# POWER_BANK_PART.net
KiCad netlist of a schematic drawn in Altium Designer
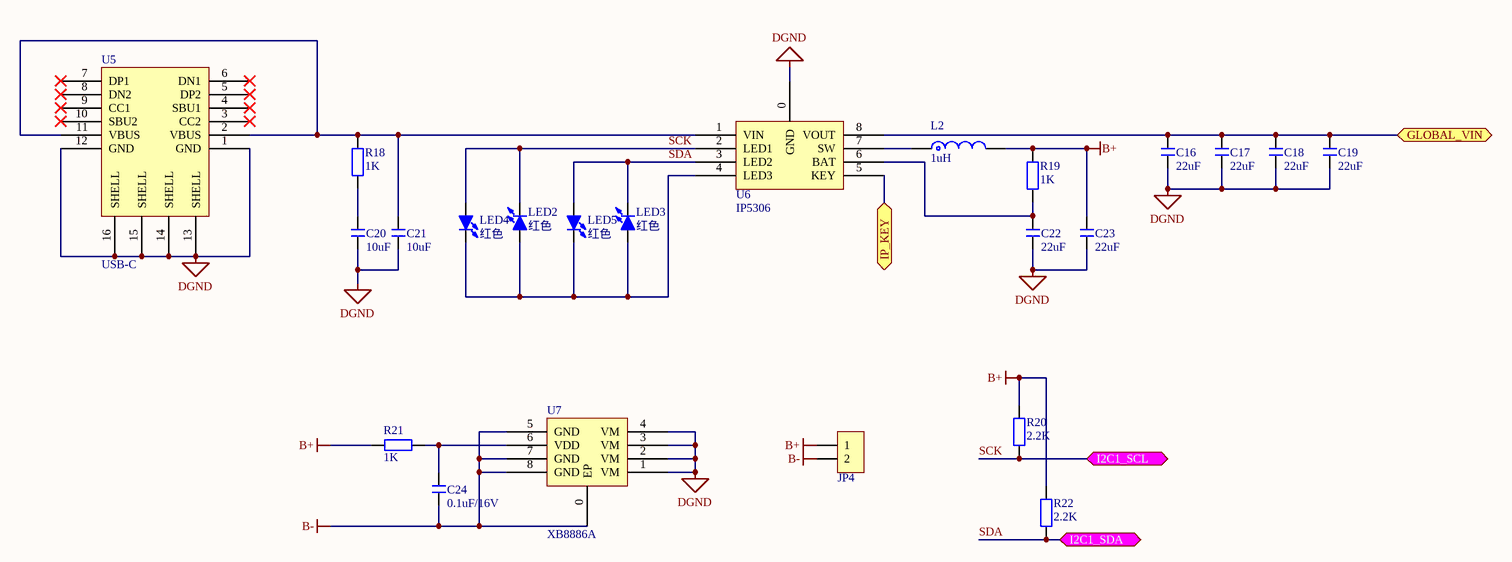
[diagram p0: POWER_BANK_PART.SchDoc]

(export (version "E")
  (design (tool "Eeschema 10.0.6"))
  (components
    (comp (ref "C16")
      (value "22uF")
      (footprint "C 0603_L")
      (description "无极性贴片电容")
      (fields (field (name "版权归属") "源创客"))
      (libsource (lib "3.1   - 电阻-电容-电感") (part "C"))
    )
    (comp (ref "C17")
      (value "22uF")
      (footprint "C 0603_L")
      (description "无极性贴片电容")
      (fields (field (name "版权归属") "源创客"))
      (libsource (lib "3.1   - 电阻-电容-电感") (part "C"))
    )
    (comp (ref "C18")
      (value "22uF")
      (footprint "C 0603_L")
      (description "无极性贴片电容")
      (fields (field (name "版权归属") "源创客"))
      (libsource (lib "3.1   - 电阻-电容-电感") (part "C"))
    )
    (comp (ref "C19")
      (value "22uF")
      (footprint "C 0603_L")
      (description "无极性贴片电容")
      (fields (field (name "版权归属") "源创客"))
      (libsource (lib "3.1   - 电阻-电容-电感") (part "C"))
    )
    (comp (ref "C20")
      (value "10uF")
      (footprint "C 0603_L")
      (description "无极性贴片电容")
      (fields (field (name "版权归属") "源创客"))
      (libsource (lib "3.1   - 电阻-电容-电感") (part "C"))
    )
    (comp (ref "C21")
      (value "10uF")
      (footprint "C 0603_L")
      (description "无极性贴片电容")
      (fields (field (name "版权归属") "源创客"))
      (libsource (lib "3.1   - 电阻-电容-电感") (part "C"))
    )
    (comp (ref "C22")
      (value "22uF")
      (footprint "C 0603_L")
      (description "无极性贴片电容")
      (fields (field (name "版权归属") "源创客"))
      (libsource (lib "3.1   - 电阻-电容-电感") (part "C"))
    )
    (comp (ref "C23")
      (value "22uF")
      (footprint "C 0603_L")
      (description "无极性贴片电容")
      (fields (field (name "版权归属") "源创客"))
      (libsource (lib "3.1   - 电阻-电容-电感") (part "C"))
    )
    (comp (ref "C24")
      (value "0.1uF/16V")
      (footprint "C 0603_L")
      (description "无极性贴片电容")
      (fields (field (name "版权归属") "源创客"))
      (libsource (lib "3.1   - 电阻-电容-电感") (part "C"))
    )
    (comp (ref "JP4")
      (value "HDR-1X2")
      (footprint "KF301-5.0-2P")
      (description "2P接插件")
      (fields (field (name "版权归属") "源创客"))
      (libsource (lib "4.9   - 接插件-脚距5.0") (part "Header 2"))
    )
    (comp (ref "L2")
      (value "1uH")
      (footprint "CD43")
      (description "贴片功率电感")
      (fields (field (name "版权归属") "源创客"))
      (libsource (lib "3.1   - 电阻-电容-电感") (part "L-CD"))
    )
    (comp (ref "LED2")
      (value "红色")
      (footprint "LED 0603W")
      (description "贴片LED")
      (fields (field (name "版权归属") "源创客"))
      (libsource (lib "9.1   - LED") (part "LED-SMD"))
    )
    (comp (ref "LED3")
      (value "红色")
      (footprint "LED 0603W")
      (description "贴片LED")
      (fields (field (name "版权归属") "源创客"))
      (libsource (lib "9.1   - LED") (part "LED-SMD"))
    )
    (comp (ref "LED4")
      (value "红色")
      (footprint "LED 0603W")
      (description "贴片LED")
      (fields (field (name "版权归属") "源创客"))
      (libsource (lib "9.1   - LED") (part "LED-SMD"))
    )
    (comp (ref "LED5")
      (value "红色")
      (footprint "LED 0603W")
      (description "贴片LED")
      (fields (field (name "版权归属") "源创客"))
      (libsource (lib "9.1   - LED") (part "LED-SMD"))
    )
    (comp (ref "R18")
      (value "1K")
      (footprint "R 0603_L")
      (description "贴片电阻")
      (fields (field (name "版权归属") "源创客"))
      (libsource (lib "3.1   - 电阻-电容-电感") (part "R"))
    )
    (comp (ref "R19")
      (value "1K")
      (footprint "R 0603_L")
      (description "贴片电阻")
      (fields (field (name "版权归属") "源创客"))
      (libsource (lib "3.1   - 电阻-电容-电感") (part "R"))
    )
    (comp (ref "R20")
      (value "2.2K")
      (footprint "R 0603_L")
      (description "贴片电阻")
      (fields (field (name "版权归属") "源创客"))
      (libsource (lib "3.1   - 电阻-电容-电感") (part "R"))
    )
    (comp (ref "R21")
      (value "1K")
      (footprint "R 0603_L")
      (description "贴片电阻")
      (fields (field (name "版权归属") "源创客"))
      (libsource (lib "3.1   - 电阻-电容-电感") (part "R"))
    )
    (comp (ref "R22")
      (value "2.2K")
      (footprint "R 0603_L")
      (description "贴片电阻")
      (fields (field (name "版权归属") "源创客"))
      (libsource (lib "3.1   - 电阻-电容-电感") (part "R"))
    )
    (comp (ref "U5")
      (value "USB-C")
      (footprint "USB-C-16")
      (description "USB-C型母接口")
      (fields (field (name "版权归属") "源创客"))
      (libsource (lib "示波器") (part "USB-C-16P"))
    )
    (comp (ref "U6")
      (value "IP5306")
      (footprint "SOP-8-G")
      (description "电源芯片")
      (libsource (lib "示波器") (part "IP5306"))
    )
    (comp (ref "U7")
      (value "XB8886A")
      (footprint "SOP-8-G")
      (description "锂电池保护芯片")
      (libsource (lib "示波器") (part "XB8886A"))
    )
  )
  (nets
    (net (code "1") (name "/GLOBAL_VIN") (class "Default")
      (node (ref "C16") (pin "1") (pinfunction "1_1") (pintype "passive"))
      (node (ref "C17") (pin "1") (pinfunction "1_1") (pintype "passive"))
      (node (ref "C18") (pin "1") (pinfunction "1_1") (pintype "passive"))
      (node (ref "C19") (pin "1") (pinfunction "1_1") (pintype "passive"))
      (node (ref "U6") (pin "8") (pinfunction "VOUT_8") (pintype "passive"))
    )
    (net (code "2") (name "/IP_KEY") (class "Default")
      (node (ref "U6") (pin "5") (pinfunction "KEY_5") (pintype "passive"))
    )
    (net (code "3") (name "/SCK") (class "Default")
      (node (ref "LED2") (pin "2") (pinfunction "K_2") (pintype "passive"))
      (node (ref "LED4") (pin "1") (pinfunction "A_1") (pintype "passive"))
      (node (ref "R20") (pin "1") (pinfunction "1_1") (pintype "passive"))
      (node (ref "U6") (pin "2") (pinfunction "LED1_2") (pintype "passive"))
    )
    (net (code "4") (name "/SDA") (class "Default")
      (node (ref "LED3") (pin "2") (pinfunction "K_2") (pintype "passive"))
      (node (ref "LED5") (pin "1") (pinfunction "A_1") (pintype "passive"))
      (node (ref "R22") (pin "1") (pinfunction "1_1") (pintype "passive"))
      (node (ref "U6") (pin "3") (pinfunction "LED2_3") (pintype "passive"))
    )
    (net (code "5") (name "B+") (class "Default")
      (node (ref "C23") (pin "1") (pinfunction "1_1") (pintype "passive"))
      (node (ref "JP4") (pin "1") (pinfunction "1_1") (pintype "passive"))
      (node (ref "L2") (pin "2") (pinfunction "2_2") (pintype "passive"))
      (node (ref "R19") (pin "2") (pinfunction "2_2") (pintype "passive"))
      (node (ref "R20") (pin "2") (pinfunction "2_2") (pintype "passive"))
      (node (ref "R21") (pin "1") (pinfunction "1_1") (pintype "passive"))
      (node (ref "R22") (pin "2") (pinfunction "2_2") (pintype "passive"))
    )
    (net (code "6") (name "B-") (class "Default")
      (node (ref "C24") (pin "2") (pinfunction "2_2") (pintype "passive"))
      (node (ref "JP4") (pin "2") (pinfunction "2_2") (pintype "passive"))
      (node (ref "U7") (pin "0") (pinfunction "EP_0") (pintype "passive"))
      (node (ref "U7") (pin "5") (pinfunction "GND_5") (pintype "passive"))
      (node (ref "U7") (pin "7") (pinfunction "GND_7") (pintype "passive"))
      (node (ref "U7") (pin "8") (pinfunction "GND_8") (pintype "passive"))
    )
    (net (code "7") (name "DGND") (class "Default")
      (node (ref "C16") (pin "2") (pinfunction "2_2") (pintype "passive"))
      (node (ref "C17") (pin "2") (pinfunction "2_2") (pintype "passive"))
      (node (ref "C18") (pin "2") (pinfunction "2_2") (pintype "passive"))
      (node (ref "C19") (pin "2") (pinfunction "2_2") (pintype "passive"))
      (node (ref "C20") (pin "2") (pinfunction "2_2") (pintype "passive"))
      (node (ref "C21") (pin "2") (pinfunction "2_2") (pintype "passive"))
      (node (ref "C22") (pin "2") (pinfunction "2_2") (pintype "passive"))
      (node (ref "C23") (pin "2") (pinfunction "2_2") (pintype "passive"))
      (node (ref "U5") (pin "1") (pinfunction "GND_1") (pintype "passive"))
      (node (ref "U5") (pin "12") (pinfunction "GND_12") (pintype "passive"))
      (node (ref "U5") (pin "13") (pinfunction "SHELL_13") (pintype "passive"))
      (node (ref "U5") (pin "14") (pinfunction "SHELL_14") (pintype "passive"))
      (node (ref "U5") (pin "15") (pinfunction "SHELL_15") (pintype "passive"))
      (node (ref "U5") (pin "16") (pinfunction "SHELL_16") (pintype "passive"))
      (node (ref "U6") (pin "0") (pinfunction "GND_0") (pintype "passive"))
      (node (ref "U7") (pin "1") (pinfunction "VM_1") (pintype "passive"))
      (node (ref "U7") (pin "2") (pinfunction "VM_2") (pintype "passive"))
      (node (ref "U7") (pin "3") (pinfunction "VM_3") (pintype "passive"))
      (node (ref "U7") (pin "4") (pinfunction "VM_4") (pintype "passive"))
    )
    (net (code "8") (name "Net-(C20-Pad1)") (class "Default")
      (node (ref "C20") (pin "1") (pinfunction "1_1") (pintype "passive"))
      (node (ref "R18") (pin "1") (pinfunction "1_1") (pintype "passive"))
    )
    (net (code "9") (name "Net-(LED2-A)") (class "Default")
      (node (ref "LED2") (pin "1") (pinfunction "A_1") (pintype "passive"))
      (node (ref "LED3") (pin "1") (pinfunction "A_1") (pintype "passive"))
      (node (ref "LED4") (pin "2") (pinfunction "K_2") (pintype "passive"))
      (node (ref "LED5") (pin "2") (pinfunction "K_2") (pintype "passive"))
      (node (ref "U6") (pin "4") (pinfunction "LED3_4") (pintype "passive"))
    )
    (net (code "10") (name "Net-(U6-BAT)") (class "Default")
      (node (ref "C22") (pin "1") (pinfunction "1_1") (pintype "passive"))
      (node (ref "R19") (pin "1") (pinfunction "1_1") (pintype "passive"))
      (node (ref "U6") (pin "6") (pinfunction "BAT_6") (pintype "passive"))
    )
    (net (code "11") (name "Net-(U6-SW)") (class "Default")
      (node (ref "L2") (pin "1") (pinfunction "1_1") (pintype "passive"))
      (node (ref "U6") (pin "7") (pinfunction "SW_7") (pintype "passive"))
    )
    (net (code "12") (name "Net-(U6-VIN)") (class "Default")
      (node (ref "C21") (pin "1") (pinfunction "1_1") (pintype "passive"))
      (node (ref "R18") (pin "2") (pinfunction "2_2") (pintype "passive"))
      (node (ref "U5") (pin "11") (pinfunction "VBUS_11") (pintype "passive"))
      (node (ref "U5") (pin "2") (pinfunction "VBUS_2") (pintype "passive"))
      (node (ref "U6") (pin "1") (pinfunction "VIN_1") (pintype "passive"))
    )
    (net (code "13") (name "Net-(U7-VDD)") (class "Default")
      (node (ref "C24") (pin "1") (pinfunction "1_1") (pintype "passive"))
      (node (ref "R21") (pin "2") (pinfunction "2_2") (pintype "passive"))
      (node (ref "U7") (pin "6") (pinfunction "VDD_6") (pintype "passive"))
    )
    (net (code "14") (name "unconnected-(U5-CC1-Pad9)") (class "Default")
      (node (ref "U5") (pin "9") (pinfunction "CC1_9") (pintype "passive+no_connect"))
    )
    (net (code "15") (name "unconnected-(U5-CC2-Pad3)") (class "Default")
      (node (ref "U5") (pin "3") (pinfunction "CC2_3") (pintype "passive+no_connect"))
    )
    (net (code "16") (name "unconnected-(U5-DN1-Pad6)") (class "Default")
      (node (ref "U5") (pin "6") (pinfunction "DN1_6") (pintype "passive+no_connect"))
    )
    (net (code "17") (name "unconnected-(U5-DN2-Pad8)") (class "Default")
      (node (ref "U5") (pin "8") (pinfunction "DN2_8") (pintype "passive+no_connect"))
    )
    (net (code "18") (name "unconnected-(U5-DP1-Pad7)") (class "Default")
      (node (ref "U5") (pin "7") (pinfunction "DP1_7") (pintype "passive+no_connect"))
    )
    (net (code "19") (name "unconnected-(U5-DP2-Pad5)") (class "Default")
      (node (ref "U5") (pin "5") (pinfunction "DP2_5") (pintype "passive+no_connect"))
    )
    (net (code "20") (name "unconnected-(U5-SBU1-Pad4)") (class "Default")
      (node (ref "U5") (pin "4") (pinfunction "SBU1_4") (pintype "passive+no_connect"))
    )
    (net (code "21") (name "unconnected-(U5-SBU2-Pad10)") (class "Default")
      (node (ref "U5") (pin "10") (pinfunction "SBU2_10") (pintype "passive+no_connect"))
    )
  )
)
